# PSU.net
KiCad netlist of a schematic drawn in Altium Designer
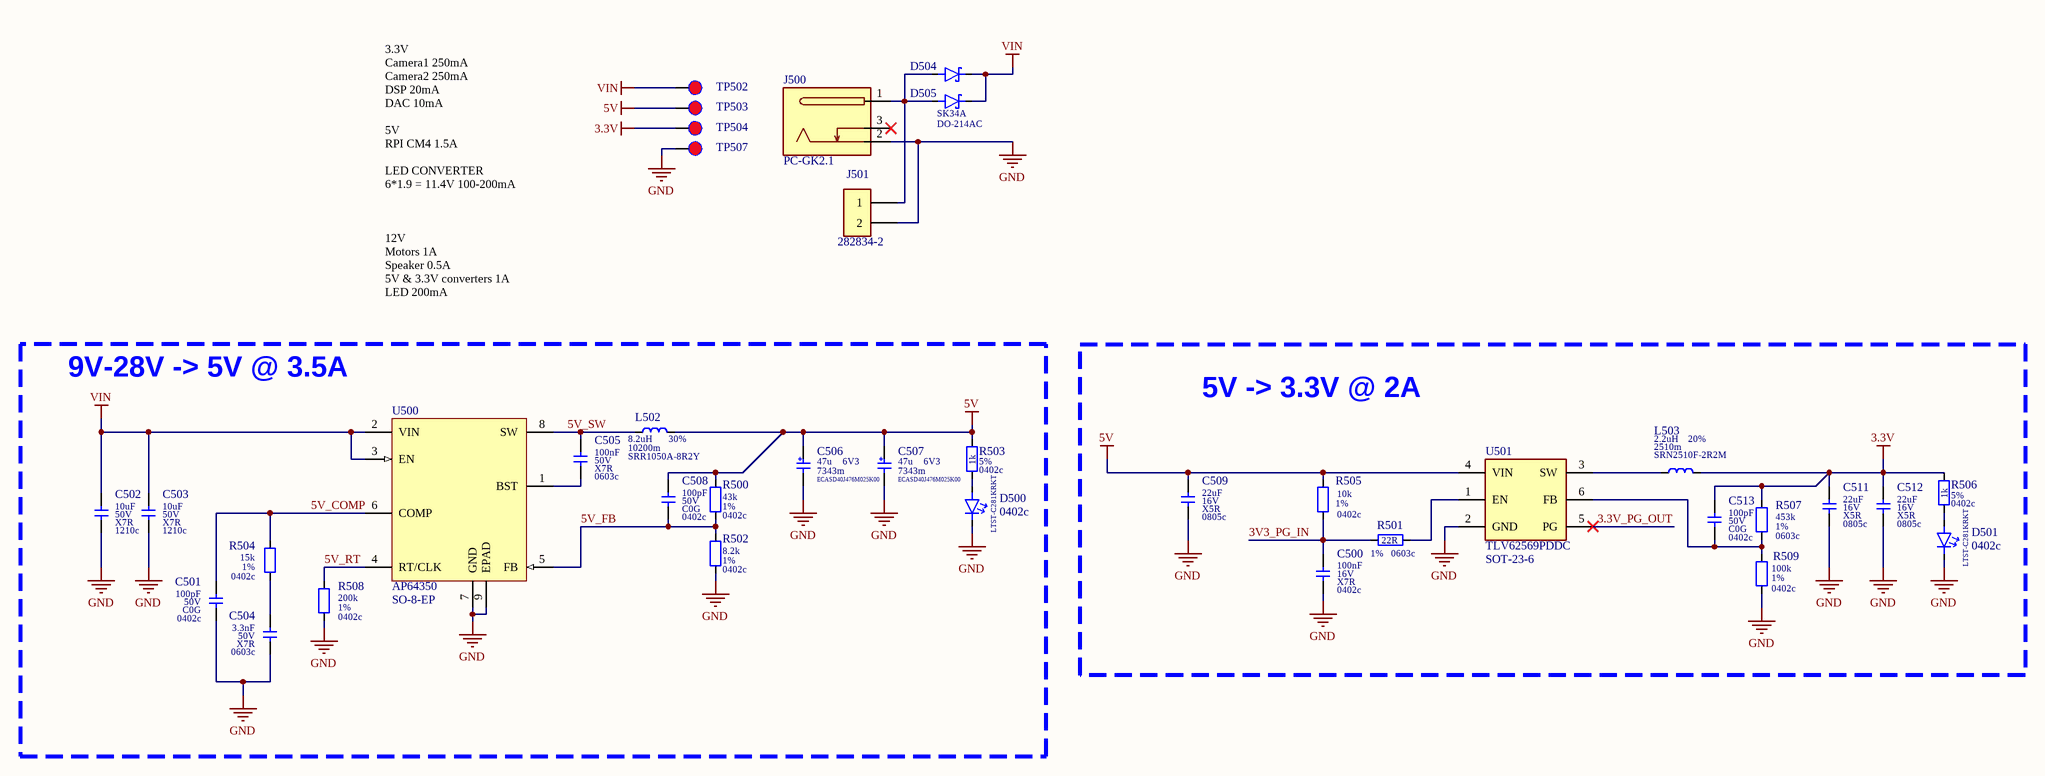
[diagram p0: PSU.SchDoc]

(export (version "E")
  (design (tool "Eeschema 10.0.6"))
  (components
    (comp (ref "C500")
      (value "CL05B104KO5NNNC")
      (footprint "CAPC1005X60L")
      (description "SMT 0402c 100nF 16V 10% X7R 25.8MHz 125'C")
      (fields
        (field (name "11 PARAMETER 4") "X7R")
        (field (name "07 PACKAGE") "0402c")
        (field (name "08 PARAMETER 1") "100nF")
        (field (name "09 PARAMETER 2") "16V")
      )
      (libsource (lib "MS_Altium_Lib") (part "CAPACITOR"))
    )
    (comp (ref "C501")
      (value "GRM1555C1H101JA01D")
      (footprint "CAPC1005X60L")
      (description "SMT 0402c 100pF 50V 5% C0G 814MHz 125'C")
      (fields
        (field (name "11 PARAMETER 4") "C0G")
        (field (name "07 PACKAGE") "0402c")
        (field (name "08 PARAMETER 1") "100pF")
        (field (name "09 PARAMETER 2") "50V")
      )
      (libsource (lib "MS_Altium_Lib") (part "CAPACITOR"))
    )
    (comp (ref "C502")
      (value "CL32B106KBJNNNE")
      (footprint "CAPC3225X270L")
      (description "SMT 1210c 10uF 50V 10% X7R 125°C")
      (fields
        (field (name "11 PARAMETER 4") "X7R")
        (field (name "07 PACKAGE") "1210c")
        (field (name "08 PARAMETER 1") "10uF")
        (field (name "09 PARAMETER 2") "50V")
      )
      (libsource (lib "MS_Altium_Lib") (part "CAPACITOR"))
    )
    (comp (ref "C503")
      (value "CL32B106KBJNNNE")
      (footprint "CAPC3225X270L")
      (description "SMT 1210c 10uF 50V 10% X7R 125°C")
      (fields
        (field (name "11 PARAMETER 4") "X7R")
        (field (name "07 PACKAGE") "1210c")
        (field (name "08 PARAMETER 1") "10uF")
        (field (name "09 PARAMETER 2") "50V")
      )
      (libsource (lib "MS_Altium_Lib") (part "CAPACITOR"))
    )
    (comp (ref "C504")
      (value "CL10B332KB8NNNC")
      (footprint "CAPC1608X90L")
      (description "SMT 0603c 3.3nF 50V 10% X7R 125°C")
      (fields
        (field (name "11 PARAMETER 4") "X7R")
        (field (name "07 PACKAGE") "0603c")
        (field (name "08 PARAMETER 1") "3.3nF")
        (field (name "09 PARAMETER 2") "50V")
      )
      (libsource (lib "MS_Altium_Lib") (part "CAPACITOR"))
    )
    (comp (ref "C505")
      (value "CL10B104KB8NNNC")
      (footprint "CAPC1608X90L")
      (description "SMT 0603c 100nF 50V 10% X7R 125'C")
      (fields
        (field (name "11 PARAMETER 4") "X7R")
        (field (name "07 PACKAGE") "0603c")
        (field (name "08 PARAMETER 1") "100nF")
        (field (name "09 PARAMETER 2") "50V")
      )
      (libsource (lib "MS_Altium_Lib") (part "CAPACITOR"))
    )
    (comp (ref "C506")
      (value "ECASD40J476M025K00")
      (footprint "CAPMP7343X20L")
      (description "SMT 7343m 47u 6V3 20% 25mOhm 1.8A 105°C")
      (fields
        (field (name "09 PARAMETER 2") "6V3")
        (field (name "08 PARAMETER 1") "47u")
        (field (name "02 MPN") "ECASD40J476M025K00")
        (field (name "07 PACKAGE") "7343m")
      )
      (libsource (lib "MS_Altium_Lib") (part "CAPACITOR POLARIZED"))
    )
    (comp (ref "C507")
      (value "ECASD40J476M025K00")
      (footprint "CAPMP7343X20L")
      (description "SMT 7343m 47u 6V3 20% 25mOhm 1.8A 105°C")
      (fields
        (field (name "09 PARAMETER 2") "6V3")
        (field (name "08 PARAMETER 1") "47u")
        (field (name "02 MPN") "ECASD40J476M025K00")
        (field (name "07 PACKAGE") "7343m")
      )
      (libsource (lib "MS_Altium_Lib") (part "CAPACITOR POLARIZED"))
    )
    (comp (ref "C508")
      (value "GRM1555C1H101JA01D")
      (footprint "CAPC1005X60L")
      (description "SMT 0402c 100pF 50V 5% C0G 814MHz 125'C")
      (fields
        (field (name "11 PARAMETER 4") "C0G")
        (field (name "07 PACKAGE") "0402c")
        (field (name "08 PARAMETER 1") "100pF")
        (field (name "09 PARAMETER 2") "50V")
      )
      (libsource (lib "MS_Altium_Lib") (part "CAPACITOR"))
    )
    (comp (ref "C509")
      (value "CL21A226MOQNNNE")
      (footprint "CAPC2013X145L")
      (description "SMT 0805c 22uF 16V 20% X5R 1.6MHz 85'C")
      (fields
        (field (name "11 PARAMETER 4") "X5R")
        (field (name "07 PACKAGE") "0805c")
        (field (name "08 PARAMETER 1") "22uF")
        (field (name "09 PARAMETER 2") "16V")
      )
      (libsource (lib "MS_Altium_Lib") (part "CAPACITOR"))
    )
    (comp (ref "C511")
      (value "CL21A226MOQNNNE")
      (footprint "CAPC2013X145L")
      (description "SMT 0805c 22uF 16V 20% X5R 1.6MHz 85'C")
      (fields
        (field (name "11 PARAMETER 4") "X5R")
        (field (name "07 PACKAGE") "0805c")
        (field (name "08 PARAMETER 1") "22uF")
        (field (name "09 PARAMETER 2") "16V")
      )
      (libsource (lib "MS_Altium_Lib") (part "CAPACITOR"))
    )
    (comp (ref "C512")
      (value "CL21A226MOQNNNE")
      (footprint "CAPC2013X145L")
      (description "SMT 0805c 22uF 16V 20% X5R 1.6MHz 85'C")
      (fields
        (field (name "11 PARAMETER 4") "X5R")
        (field (name "07 PACKAGE") "0805c")
        (field (name "08 PARAMETER 1") "22uF")
        (field (name "09 PARAMETER 2") "16V")
      )
      (libsource (lib "MS_Altium_Lib") (part "CAPACITOR"))
    )
    (comp (ref "C513")
      (value "GRM1555C1H101JA01D")
      (footprint "CAPC1005X60L")
      (description "SMT 0402c 100pF 50V 5% C0G 814MHz 125'C")
      (fields
        (field (name "11 PARAMETER 4") "C0G")
        (field (name "07 PACKAGE") "0402c")
        (field (name "08 PARAMETER 1") "100pF")
        (field (name "09 PARAMETER 2") "50V")
      )
      (libsource (lib "MS_Altium_Lib") (part "CAPACITOR"))
    )
    (comp (ref "D500")
      (value "LTST-C281KRKT")
      (footprint "LEDSC100x50x35-2L")
      (description "SMT 0402c RED Striaight 18...54mcd  130deg 2.0V")
      (fields (field (name "02 MPN") "LTST-C281KRKT") (field (name "07 PACKAGE") "0402c"))
      (libsource (lib "MS_Altium_Lib") (part "LED"))
    )
    (comp (ref "D501")
      (value "LTST-C281KRKT")
      (footprint "LEDSC100x50x35-2L")
      (description "SMT 0402c RED Striaight 18...54mcd  130deg 2.0V")
      (fields (field (name "02 MPN") "LTST-C281KRKT") (field (name "07 PACKAGE") "0402c"))
      (libsource (lib "MS_Altium_Lib") (part "LED"))
    )
    (comp (ref "D504")
      (value "SK34A")
      (footprint "DIOM4326X250L")
      (description "SMT DO-214AC 40V 3A 0.55V 70A 500uA")
      (libsource (lib "MS_Altium_Lib") (part "SCHOTTKY"))
    )
    (comp (ref "D505")
      (value "SK34A")
      (footprint "DIOM4326X250L")
      (description "SMT DO-214AC 40V 3A 0.55V 70A 500uA")
      (fields (field (name "02 MPN") "SK34A") (field (name "07 PACKAGE") "DO-214AC"))
      (libsource (lib "MS_Altium_Lib") (part "SCHOTTKY"))
    )
    (comp (ref "J500")
      (value "PC-GK2.1")
      (footprint "NINIGI PC-GK2.1")
      (description "THT DC BARREL JACK Right Angle")
      (fields (field (name "02 MPN") "PC-GK2.1"))
      (libsource (lib "MS_Altium_Lib") (part "NINIGI PC-GK2.1"))
    )
    (comp (ref "J501")
      (value "282834-2")
      (footprint "TE 282834-2")
      (description "THT 1x2 2.54mm Straight 150V 10A")
      (fields (field (name "02 MPN") "282834-2"))
      (libsource (lib "MS_Altium_Lib") (part "CONNECTOR 1X2"))
    )
    (comp (ref "L502")
      (value "SRR1050A-8R2Y")
      (footprint "IND102100X51L")
      (description "SMT 10200m 8.2uH 0,3 5A 4.85A 22mOhm 21MHz")
      (fields
        (field (name "09 PARAMETER 2") "30%")
        (field (name "08 PARAMETER 1") "8.2uH")
        (field (name "02 MPN") "SRR1050A-8R2Y")
        (field (name "07 PACKAGE") "10200m")
      )
      (libsource (lib "MS_Altium_Lib") (part "INDUCTOR"))
    )
    (comp (ref "L503")
      (value "SRN2510F-2R2M")
      (footprint "IND2510X10L")
      (description "SMT 2510m 2.2uH 0,2 2.6A 2.8A 78mOhm 40MHz")
      (fields
        (field (name "09 PARAMETER 2") "20%")
        (field (name "08 PARAMETER 1") "2.2uH")
        (field (name "02 MPN") "SRN2510F-2R2M")
        (field (name "07 PACKAGE") "2510m")
      )
      (libsource (lib "MS_Altium_Lib") (part "INDUCTOR"))
    )
    (comp (ref "R500")
      (value "RC0402FR-0743KL")
      (footprint "RESC1005X40L")
      (description "SMT 0402c 43k 1% 62.5mW 100ppm/K 50V")
      (fields
        (field (name "07 PACKAGE") "0402c")
        (field (name "09 PARAMETER 2") "1%")
        (field (name "08 PARAMETER 1") "43k")
      )
      (libsource (lib "MS_Altium_Lib") (part "RESISTOR"))
    )
    (comp (ref "R501")
      (value "RC0603FR-0722RL")
      (footprint "RESC1608X55L")
      (description "SMT 0603c 22R 1% 100mW 100ppm/K 75V")
      (fields
        (field (name "07 PACKAGE") "0603c")
        (field (name "09 PARAMETER 2") "1%")
        (field (name "08 PARAMETER 1") "22R")
      )
      (libsource (lib "") (part "RESISTOR_1"))
    )
    (comp (ref "R502")
      (value "RC0402FR-078K2L")
      (footprint "RESC1005X40L")
      (description "SMT 0402c 8.2k 1% 62.5mW 100ppm/K 50V")
      (fields
        (field (name "07 PACKAGE") "0402c")
        (field (name "09 PARAMETER 2") "1%")
        (field (name "08 PARAMETER 1") "8.2k")
      )
      (libsource (lib "MS_Altium_Lib") (part "RESISTOR"))
    )
    (comp (ref "R503")
      (value "RC0402JR-071KL")
      (footprint "RESC1005X40L")
      (description "SMT 0402c 1k 5% 62.5mW 200ppm/K 50V")
      (fields
        (field (name "07 PACKAGE") "0402c")
        (field (name "09 PARAMETER 2") "5%")
        (field (name "08 PARAMETER 1") "1k")
      )
      (libsource (lib "MS_Altium_Lib") (part "RESISTOR"))
    )
    (comp (ref "R504")
      (value "RC0402FR-0715KL")
      (footprint "RESC1005X40L")
      (description "SMT 0402c 15k 1% 62.5mW 100ppm/K 50V")
      (fields
        (field (name "07 PACKAGE") "0402c")
        (field (name "09 PARAMETER 2") "1%")
        (field (name "08 PARAMETER 1") "15k")
      )
      (libsource (lib "") (part "RESISTOR_1"))
    )
    (comp (ref "R505")
      (value "RC0402FR-0710KL")
      (footprint "RESC1005X40L")
      (description "SMT 0402c 10k 1% 62.5mW 100ppm/K 50V")
      (fields
        (field (name "07 PACKAGE") "0402c")
        (field (name "09 PARAMETER 2") "1%")
        (field (name "08 PARAMETER 1") "10k")
      )
      (libsource (lib "MS_Altium_Lib") (part "RESISTOR"))
    )
    (comp (ref "R506")
      (value "RC0402JR-071KL")
      (footprint "RESC1005X40L")
      (description "SMT 0402c 1k 5% 62.5mW 200ppm/K 50V")
      (fields
        (field (name "07 PACKAGE") "0402c")
        (field (name "09 PARAMETER 2") "5%")
        (field (name "08 PARAMETER 1") "1k")
      )
      (libsource (lib "MS_Altium_Lib") (part "RESISTOR"))
    )
    (comp (ref "R507")
      (value "RC0603FR-07453KL")
      (footprint "RESC1608X55L")
      (description "SMT 0603c 453k 1% 100mW 100ppm/K 75V")
      (fields
        (field (name "07 PACKAGE") "0603c")
        (field (name "09 PARAMETER 2") "1%")
        (field (name "08 PARAMETER 1") "453k")
      )
      (libsource (lib "MS_Altium_Lib") (part "RESISTOR"))
    )
    (comp (ref "R508")
      (value "RC0402FR-07200KL")
      (footprint "RESC1005X40L")
      (description "SMT 0402c 200k 1% 62.5mW 100ppm/K 50V")
      (fields
        (field (name "07 PACKAGE") "0402c")
        (field (name "09 PARAMETER 2") "1%")
        (field (name "08 PARAMETER 1") "200k")
      )
      (libsource (lib "MS_Altium_Lib") (part "RESISTOR"))
    )
    (comp (ref "R509")
      (value "RC0402FR-07100KL")
      (footprint "RESC1005X40L")
      (description "SMT 0402c 100k 1% 62.5mW 100ppm/K 50V")
      (fields
        (field (name "07 PACKAGE") "0402c")
        (field (name "09 PARAMETER 2") "1%")
        (field (name "08 PARAMETER 1") "100k")
      )
      (libsource (lib "MS_Altium_Lib") (part "RESISTOR"))
    )
    (comp (ref "TP502")
      (value "TESTPAD")
      (footprint "TP 1.2mm")
      (libsource (lib "MS_Altium_Lib") (part "TESTPAD"))
    )
    (comp (ref "TP503")
      (value "TESTPAD")
      (footprint "TP 1.2mm")
      (libsource (lib "MS_Altium_Lib") (part "TESTPAD"))
    )
    (comp (ref "TP504")
      (value "TESTPAD")
      (footprint "TP 1.2mm")
      (libsource (lib "MS_Altium_Lib") (part "TESTPAD"))
    )
    (comp (ref "TP507")
      (value "TESTPAD")
      (footprint "TP 1.2mm")
      (libsource (lib "MS_Altium_Lib") (part "TESTPAD"))
    )
    (comp (ref "U500")
      (value "AP64350")
      (footprint "SOIC127P600X170_HS350x261-9L")
      (description "SMT SO-8-EP 40V 3.5A 100kHz - 2.2MHz")
      (fields (field (name "02 MPN") "AP64350") (field (name "07 PACKAGE") "SO-8-EP"))
      (libsource (lib "MS_Altium_Lib") (part "AP64350"))
    )
    (comp (ref "U501")
      (value "TLV62569PDDC")
      (footprint "SOT95P280X110-6L")
      (description "SMT SOT-23-6 5.5V 2A 1.5MHz")
      (fields (field (name "02 MPN") "TLV62569PDDC") (field (name "07 PACKAGE") "SOT-23-6"))
      (libsource (lib "MS_Altium_Lib") (part "TLV62569PDDC"))
    )
  )
  (nets
    (net (code "1") (name "/3.3V_PG_OUT") (class "Default")
      (node (ref "U501") (pin "5") (pinfunction "PG_5") (pintype "passive+no_connect"))
    )
    (net (code "2") (name "/3V3_PG_IN") (class "Default")
      (node (ref "C500") (pin "2") (pinfunction "2_2") (pintype "passive"))
      (node (ref "R501") (pin "1") (pinfunction "1_1") (pintype "passive"))
      (node (ref "R505") (pin "1") (pinfunction "1_1") (pintype "passive"))
    )
    (net (code "3") (name "/5V_COMP") (class "Default")
      (node (ref "C501") (pin "2") (pinfunction "2_2") (pintype "passive"))
      (node (ref "R504") (pin "2") (pinfunction "2_2") (pintype "passive"))
      (node (ref "U500") (pin "6") (pinfunction "COMP_6") (pintype "passive"))
    )
    (net (code "4") (name "/5V_FB") (class "Default")
      (node (ref "C508") (pin "1") (pinfunction "1_1") (pintype "passive"))
      (node (ref "R500") (pin "1") (pinfunction "1_1") (pintype "passive"))
      (node (ref "R502") (pin "2") (pinfunction "2_2") (pintype "passive"))
      (node (ref "U500") (pin "5") (pinfunction "FB_5") (pintype "input"))
    )
    (net (code "5") (name "/5V_RT") (class "Default")
      (node (ref "R508") (pin "2") (pinfunction "2_2") (pintype "passive"))
      (node (ref "U500") (pin "4") (pinfunction "RT/CLK_4") (pintype "passive"))
    )
    (net (code "6") (name "/5V_SW") (class "Default")
      (node (ref "C505") (pin "2") (pinfunction "2_2") (pintype "passive"))
      (node (ref "L502") (pin "1") (pinfunction "1_1") (pintype "passive"))
      (node (ref "U500") (pin "8") (pinfunction "SW_8") (pintype "passive"))
    )
    (net (code "7") (name "3.3V") (class "Default")
      (node (ref "C511") (pin "2") (pinfunction "2_2") (pintype "passive"))
      (node (ref "C512") (pin "2") (pinfunction "2_2") (pintype "passive"))
      (node (ref "C513") (pin "2") (pinfunction "2_2") (pintype "passive"))
      (node (ref "L503") (pin "2") (pinfunction "2_2") (pintype "passive"))
      (node (ref "R506") (pin "2") (pinfunction "2_2") (pintype "passive"))
      (node (ref "R507") (pin "2") (pinfunction "2_2") (pintype "passive"))
      (node (ref "TP504") (pin "1") (pinfunction "1_1") (pintype "passive"))
    )
    (net (code "8") (name "5V") (class "Default")
      (node (ref "C506") (pin "1") (pinfunction "1_1") (pintype "passive"))
      (node (ref "C507") (pin "1") (pinfunction "1_1") (pintype "passive"))
      (node (ref "C508") (pin "2") (pinfunction "2_2") (pintype "passive"))
      (node (ref "C509") (pin "2") (pinfunction "2_2") (pintype "passive"))
      (node (ref "L502") (pin "2") (pinfunction "2_2") (pintype "passive"))
      (node (ref "R500") (pin "2") (pinfunction "2_2") (pintype "passive"))
      (node (ref "R503") (pin "2") (pinfunction "2_2") (pintype "passive"))
      (node (ref "R505") (pin "2") (pinfunction "2_2") (pintype "passive"))
      (node (ref "TP503") (pin "1") (pinfunction "1_1") (pintype "passive"))
      (node (ref "U501") (pin "4") (pinfunction "VIN_4") (pintype "power_in"))
    )
    (net (code "9") (name "GND") (class "Default")
      (node (ref "C500") (pin "1") (pinfunction "1_1") (pintype "passive"))
      (node (ref "C501") (pin "1") (pinfunction "1_1") (pintype "passive"))
      (node (ref "C502") (pin "1") (pinfunction "1_1") (pintype "passive"))
      (node (ref "C503") (pin "1") (pinfunction "1_1") (pintype "passive"))
      (node (ref "C504") (pin "1") (pinfunction "1_1") (pintype "passive"))
      (node (ref "C506") (pin "2") (pinfunction "2_2") (pintype "passive"))
      (node (ref "C507") (pin "2") (pinfunction "2_2") (pintype "passive"))
      (node (ref "C509") (pin "1") (pinfunction "1_1") (pintype "passive"))
      (node (ref "C511") (pin "1") (pinfunction "1_1") (pintype "passive"))
      (node (ref "C512") (pin "1") (pinfunction "1_1") (pintype "passive"))
      (node (ref "D500") (pin "K") (pinfunction "K_K") (pintype "passive"))
      (node (ref "D501") (pin "K") (pinfunction "K_K") (pintype "passive"))
      (node (ref "J500") (pin "2") (pintype "passive"))
      (node (ref "J501") (pin "2") (pinfunction "2_2") (pintype "passive"))
      (node (ref "R502") (pin "1") (pinfunction "1_1") (pintype "passive"))
      (node (ref "R508") (pin "1") (pinfunction "1_1") (pintype "passive"))
      (node (ref "R509") (pin "1") (pinfunction "1_1") (pintype "passive"))
      (node (ref "TP507") (pin "1") (pinfunction "1_1") (pintype "passive"))
      (node (ref "U500") (pin "7") (pinfunction "GND_7") (pintype "power_in"))
      (node (ref "U500") (pin "9") (pinfunction "EPAD_9") (pintype "power_in"))
      (node (ref "U501") (pin "2") (pinfunction "GND_2") (pintype "passive"))
    )
    (net (code "10") (name "Net-(C504-Pad2)") (class "Default")
      (node (ref "C504") (pin "2") (pinfunction "2_2") (pintype "passive"))
      (node (ref "R504") (pin "1") (pinfunction "1_1") (pintype "passive"))
    )
    (net (code "11") (name "Net-(D500-PadA)") (class "Default")
      (node (ref "D500") (pin "A") (pinfunction "A_A") (pintype "passive"))
      (node (ref "R503") (pin "1") (pinfunction "1_1") (pintype "passive"))
    )
    (net (code "12") (name "Net-(D501-PadA)") (class "Default")
      (node (ref "D501") (pin "A") (pinfunction "A_A") (pintype "passive"))
      (node (ref "R506") (pin "1") (pinfunction "1_1") (pintype "passive"))
    )
    (net (code "13") (name "Net-(D504-PadA)") (class "Default")
      (node (ref "D504") (pin "A") (pinfunction "A_A") (pintype "passive"))
      (node (ref "D505") (pin "A") (pinfunction "A_A") (pintype "passive"))
      (node (ref "J500") (pin "1") (pintype "passive"))
      (node (ref "J501") (pin "1") (pinfunction "1_1") (pintype "passive"))
    )
    (net (code "14") (name "Net-(U500-BST)") (class "Default")
      (node (ref "C505") (pin "1") (pinfunction "1_1") (pintype "passive"))
      (node (ref "U500") (pin "1") (pinfunction "BST_1") (pintype "passive"))
    )
    (net (code "15") (name "Net-(U501-EN)") (class "Default")
      (node (ref "R501") (pin "2") (pinfunction "2_2") (pintype "passive"))
      (node (ref "U501") (pin "1") (pinfunction "EN_1") (pintype "power_in"))
    )
    (net (code "16") (name "Net-(U501-FB)") (class "Default")
      (node (ref "C513") (pin "1") (pinfunction "1_1") (pintype "passive"))
      (node (ref "R507") (pin "1") (pinfunction "1_1") (pintype "passive"))
      (node (ref "R509") (pin "2") (pinfunction "2_2") (pintype "passive"))
      (node (ref "U501") (pin "6") (pinfunction "FB_6") (pintype "passive"))
    )
    (net (code "17") (name "Net-(U501-SW)") (class "Default")
      (node (ref "L503") (pin "1") (pinfunction "1_1") (pintype "passive"))
      (node (ref "U501") (pin "3") (pinfunction "SW_3") (pintype "power_in"))
    )
    (net (code "18") (name "VIN") (class "Default")
      (node (ref "C502") (pin "2") (pinfunction "2_2") (pintype "passive"))
      (node (ref "C503") (pin "2") (pinfunction "2_2") (pintype "passive"))
      (node (ref "D504") (pin "K") (pinfunction "K_K") (pintype "passive"))
      (node (ref "D505") (pin "K") (pinfunction "K_K") (pintype "passive"))
      (node (ref "TP502") (pin "1") (pinfunction "1_1") (pintype "passive"))
      (node (ref "U500") (pin "2") (pinfunction "VIN_2") (pintype "power_in"))
      (node (ref "U500") (pin "3") (pinfunction "EN_3") (pintype "input"))
    )
    (net (code "19") (name "unconnected-(J500-Pad3)") (class "Default")
      (node (ref "J500") (pin "3") (pintype "passive+no_connect"))
    )
  )
)
